# MCU.net
KiCad netlist of a schematic drawn in Altium Designer
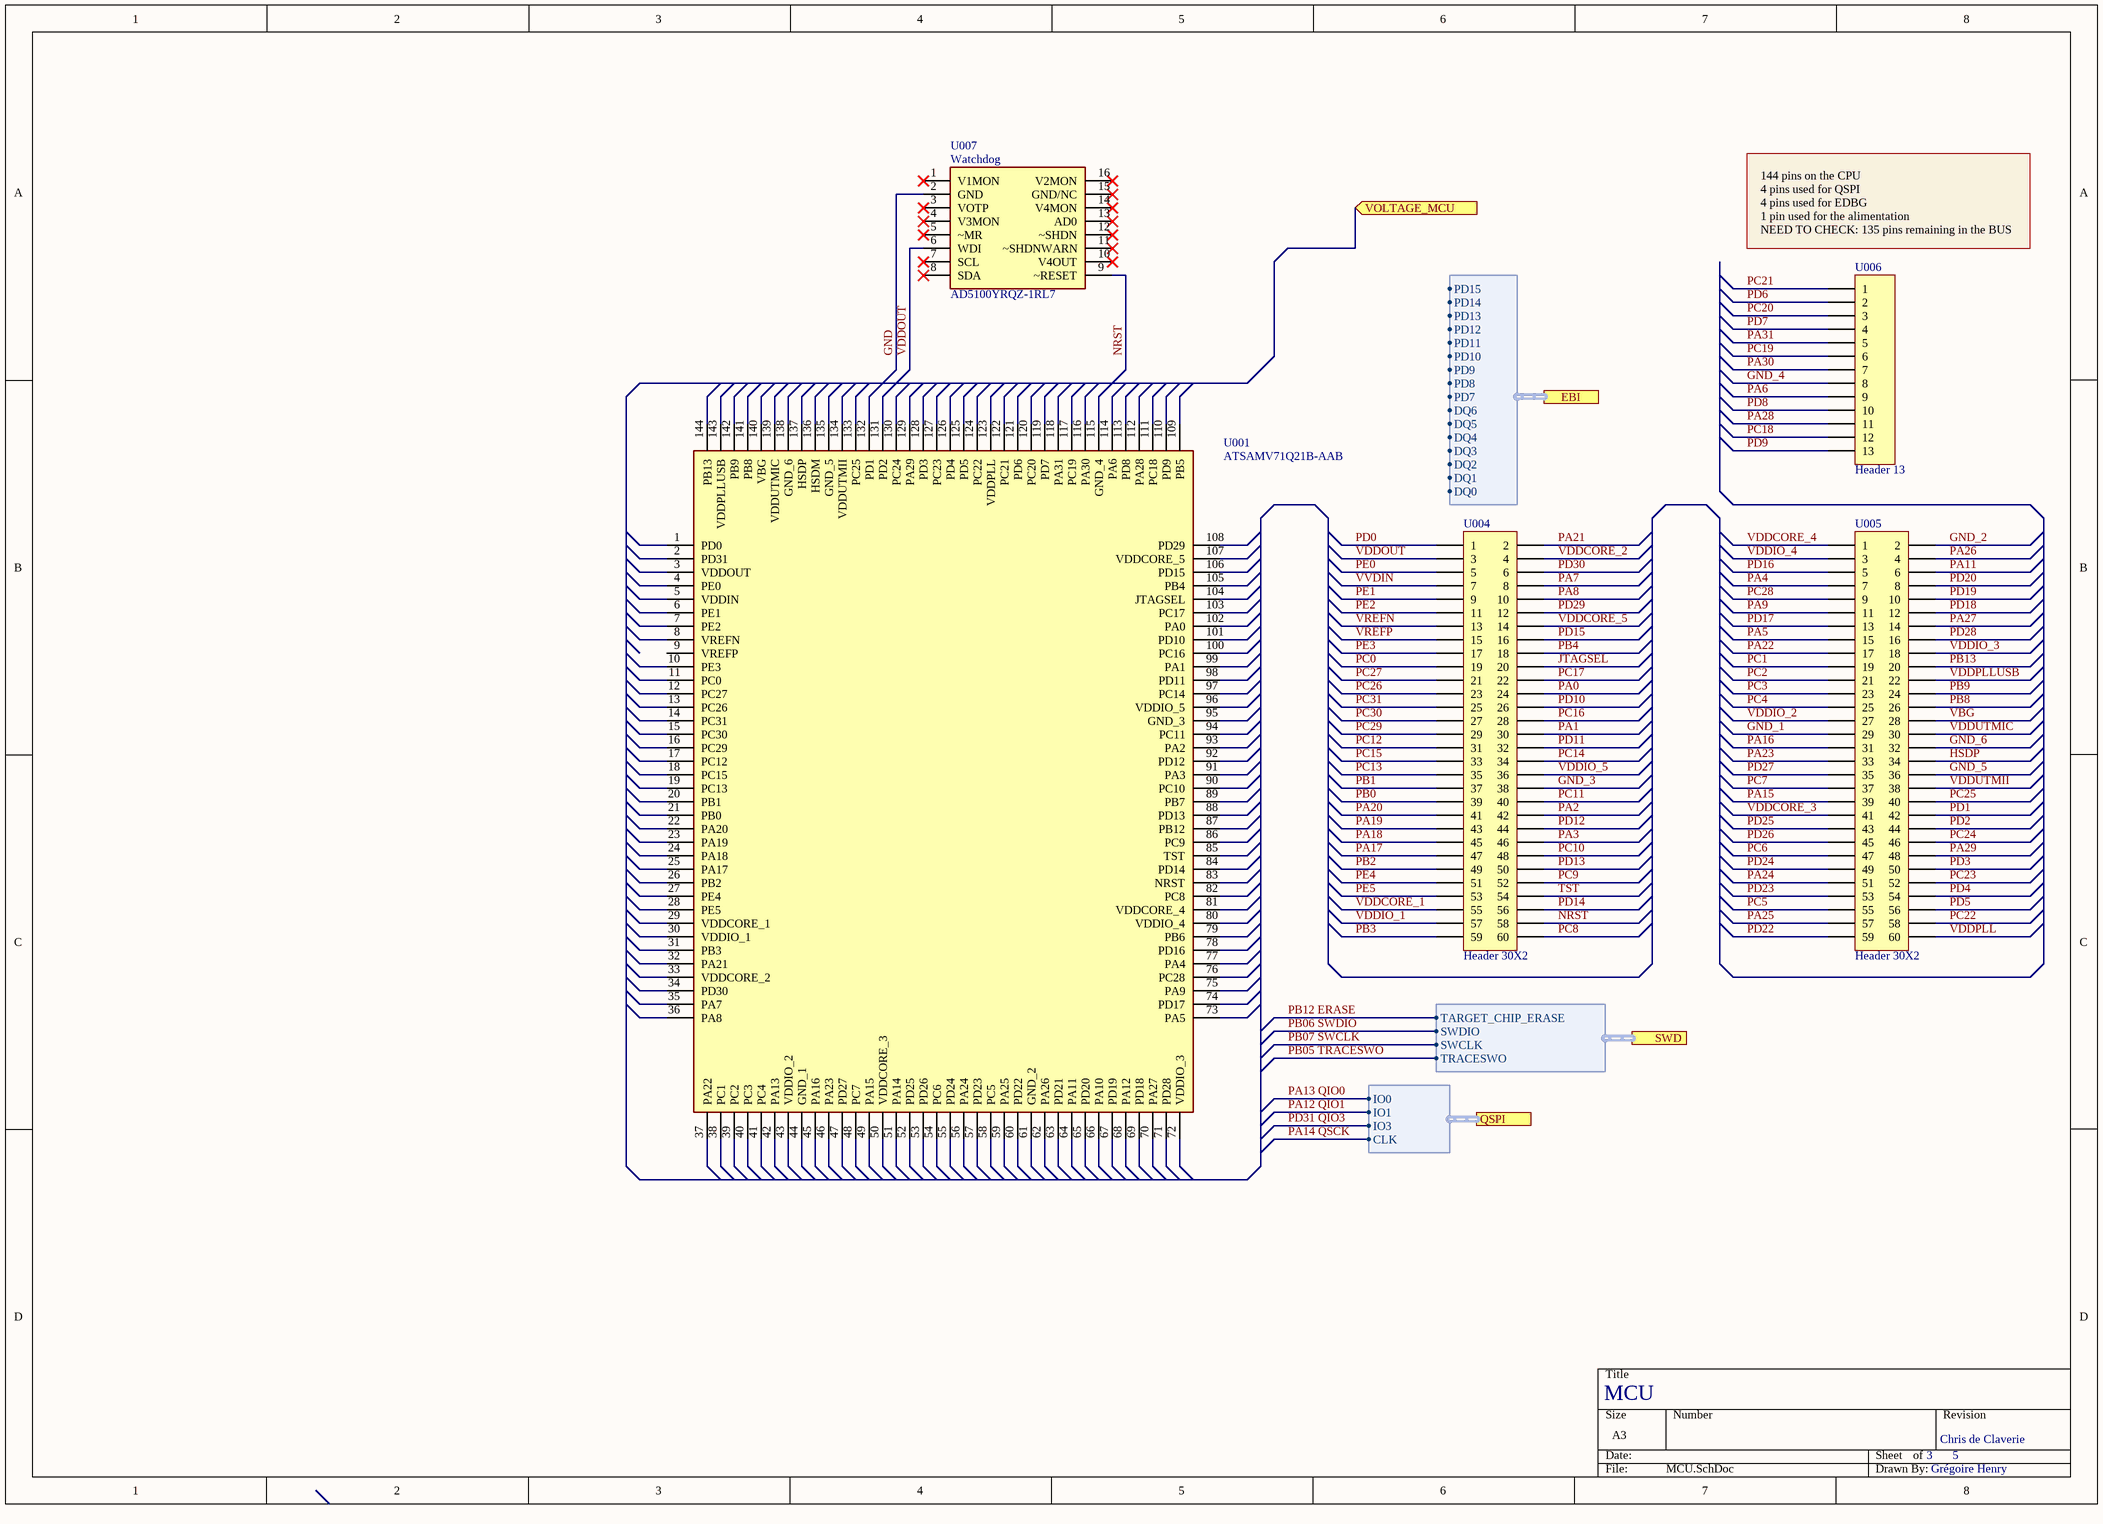
[diagram p0: MCU.SchDoc]

(export (version "E")
  (design (tool "Eeschema 10.0.6"))
  (components
    (comp (ref "U001")
      (value "ATSAMV71Q21B-AAB")
      (footprint "SamacSys:QFP50P2200X2200X160-144N")
      (description "Integrated Circuit")
      (fields (field (name "MOUSER PART NUMBER") "579-ATSAMV71Q21B-AAB"))
      (libsource (lib "*") (part "ATSAMV71Q21B-AAB"))
    )
    (comp (ref "U004")
      (value "Header 30X2")
      (footprint "HDR2X30")
      (description "Header, 30-Pin, Dual row")
      (fields (field (name "PUBLISHER") "Altium Limited"))
      (libsource (lib "Miscellaneous Connectors") (part "Header 30X2"))
    )
    (comp (ref "U005")
      (value "Header 30X2")
      (footprint "HDR2X30")
      (description "Header, 30-Pin, Dual row")
      (fields (field (name "PUBLISHER") "Altium Limited"))
      (libsource (lib "Miscellaneous Connectors") (part "Header 30X2"))
    )
    (comp (ref "U006")
      (value "Header 13")
      (footprint "HDR1X13")
      (description "Header, 13-Pin")
      (fields (field (name "PUBLISHER") "Altium Limited"))
      (libsource (lib "Miscellaneous Connectors") (part "Header 13"))
    )
    (comp (ref "U007")
      (value "AD5100YRQZ-1RL7")
      (footprint "SamacSys:SOP65P600X175-16N")
      (description "Integrated Circuit")
      (fields (field (name "MOUSER PART NUMBER") "584-AD5100YRQZ-1R7"))
      (libsource (lib "*") (part "AD5100YRQZ-1RL7"))
    )
  )
  (nets
    (net (code "2") (name "/GND") (class "Default")
      (node (ref "U007") (pin "2") (pinfunction "GND_2") (pintype "passive"))
    )
    (net (code "3") (name "/GND_1") (class "Default")
      (node (ref "U005") (pin "29") (pinfunction "29_29") (pintype "passive"))
    )
    (net (code "4") (name "/GND_2") (class "Default")
      (node (ref "U005") (pin "2") (pinfunction "2_2") (pintype "passive"))
    )
    (net (code "5") (name "/GND_3") (class "Default")
      (node (ref "U004") (pin "38") (pinfunction "38_38") (pintype "passive"))
    )
    (net (code "6") (name "/GND_4") (class "Default")
      (node (ref "U006") (pin "8") (pinfunction "8_8") (pintype "passive"))
    )
    (net (code "7") (name "/GND_5") (class "Default")
      (node (ref "U005") (pin "36") (pinfunction "36_36") (pintype "passive"))
    )
    (net (code "8") (name "/GND_6") (class "Default")
      (node (ref "U005") (pin "32") (pinfunction "32_32") (pintype "passive"))
    )
    (net (code "9") (name "/HSDP") (class "Default")
      (node (ref "U005") (pin "34") (pinfunction "34_34") (pintype "passive"))
    )
    (net (code "10") (name "/JTAGSEL") (class "Default")
      (node (ref "U004") (pin "20") (pinfunction "20_20") (pintype "passive"))
    )
    (net (code "11") (name "/NRST") (class "Default")
      (node (ref "U004") (pin "58") (pinfunction "58_58") (pintype "passive"))
      (node (ref "U007") (pin "9") (pinfunction "~RESET_9") (pintype "passive"))
    )
    (net (code "12") (name "/PA0") (class "Default")
      (node (ref "U004") (pin "24") (pinfunction "24_24") (pintype "passive"))
    )
    (net (code "13") (name "/PA1") (class "Default")
      (node (ref "U004") (pin "30") (pinfunction "30_30") (pintype "passive"))
    )
    (net (code "14") (name "/PA2") (class "Default")
      (node (ref "U004") (pin "42") (pinfunction "42_42") (pintype "passive"))
    )
    (net (code "15") (name "/PA3") (class "Default")
      (node (ref "U004") (pin "46") (pinfunction "46_46") (pintype "passive"))
    )
    (net (code "16") (name "/PA4") (class "Default")
      (node (ref "U005") (pin "7") (pinfunction "7_7") (pintype "passive"))
    )
    (net (code "17") (name "/PA5") (class "Default")
      (node (ref "U005") (pin "15") (pinfunction "15_15") (pintype "passive"))
    )
    (net (code "18") (name "/PA6") (class "Default")
      (node (ref "U006") (pin "9") (pinfunction "9_9") (pintype "passive"))
    )
    (net (code "19") (name "/PA7") (class "Default")
      (node (ref "U004") (pin "8") (pinfunction "8_8") (pintype "passive"))
    )
    (net (code "20") (name "/PA8") (class "Default")
      (node (ref "U004") (pin "10") (pinfunction "10_10") (pintype "passive"))
    )
    (net (code "21") (name "/PA9") (class "Default")
      (node (ref "U005") (pin "11") (pinfunction "11_11") (pintype "passive"))
    )
    (net (code "22") (name "/PA11") (class "Default")
      (node (ref "U005") (pin "6") (pinfunction "6_6") (pintype "passive"))
    )
    (net (code "26") (name "/PA15") (class "Default")
      (node (ref "U005") (pin "39") (pinfunction "39_39") (pintype "passive"))
    )
    (net (code "27") (name "/PA16") (class "Default")
      (node (ref "U005") (pin "31") (pinfunction "31_31") (pintype "passive"))
    )
    (net (code "28") (name "/PA17") (class "Default")
      (node (ref "U004") (pin "47") (pinfunction "47_47") (pintype "passive"))
    )
    (net (code "29") (name "/PA18") (class "Default")
      (node (ref "U004") (pin "45") (pinfunction "45_45") (pintype "passive"))
    )
    (net (code "30") (name "/PA19") (class "Default")
      (node (ref "U004") (pin "43") (pinfunction "43_43") (pintype "passive"))
    )
    (net (code "31") (name "/PA20") (class "Default")
      (node (ref "U004") (pin "41") (pinfunction "41_41") (pintype "passive"))
    )
    (net (code "32") (name "/PA21") (class "Default")
      (node (ref "U004") (pin "2") (pinfunction "2_2") (pintype "passive"))
    )
    (net (code "33") (name "/PA22") (class "Default")
      (node (ref "U005") (pin "17") (pinfunction "17_17") (pintype "passive"))
    )
    (net (code "34") (name "/PA23") (class "Default")
      (node (ref "U005") (pin "33") (pinfunction "33_33") (pintype "passive"))
    )
    (net (code "35") (name "/PA24") (class "Default")
      (node (ref "U005") (pin "51") (pinfunction "51_51") (pintype "passive"))
    )
    (net (code "36") (name "/PA25") (class "Default")
      (node (ref "U005") (pin "57") (pinfunction "57_57") (pintype "passive"))
    )
    (net (code "37") (name "/PA26") (class "Default")
      (node (ref "U005") (pin "4") (pinfunction "4_4") (pintype "passive"))
    )
    (net (code "38") (name "/PA27") (class "Default")
      (node (ref "U005") (pin "14") (pinfunction "14_14") (pintype "passive"))
    )
    (net (code "39") (name "/PA28") (class "Default")
      (node (ref "U006") (pin "11") (pinfunction "11_11") (pintype "passive"))
    )
    (net (code "40") (name "/PA29") (class "Default")
      (node (ref "U005") (pin "48") (pinfunction "48_48") (pintype "passive"))
    )
    (net (code "41") (name "/PA30") (class "Default")
      (node (ref "U006") (pin "7") (pinfunction "7_7") (pintype "passive"))
    )
    (net (code "42") (name "/PA31") (class "Default")
      (node (ref "U006") (pin "5") (pinfunction "5_5") (pintype "passive"))
    )
    (net (code "43") (name "/PB0") (class "Default")
      (node (ref "U004") (pin "39") (pinfunction "39_39") (pintype "passive"))
    )
    (net (code "44") (name "/PB1") (class "Default")
      (node (ref "U004") (pin "37") (pinfunction "37_37") (pintype "passive"))
    )
    (net (code "45") (name "/PB2") (class "Default")
      (node (ref "U004") (pin "49") (pinfunction "49_49") (pintype "passive"))
    )
    (net (code "46") (name "/PB3") (class "Default")
      (node (ref "U004") (pin "59") (pinfunction "59_59") (pintype "passive"))
    )
    (net (code "47") (name "/PB4") (class "Default")
      (node (ref "U004") (pin "18") (pinfunction "18_18") (pintype "passive"))
    )
    (net (code "51") (name "/PB8") (class "Default")
      (node (ref "U005") (pin "26") (pinfunction "26_26") (pintype "passive"))
    )
    (net (code "52") (name "/PB9") (class "Default")
      (node (ref "U005") (pin "24") (pinfunction "24_24") (pintype "passive"))
    )
    (net (code "54") (name "/PB13") (class "Default")
      (node (ref "U005") (pin "20") (pinfunction "20_20") (pintype "passive"))
    )
    (net (code "55") (name "/PC0") (class "Default")
      (node (ref "U004") (pin "19") (pinfunction "19_19") (pintype "passive"))
    )
    (net (code "56") (name "/PC1") (class "Default")
      (node (ref "U005") (pin "19") (pinfunction "19_19") (pintype "passive"))
    )
    (net (code "57") (name "/PC2") (class "Default")
      (node (ref "U005") (pin "21") (pinfunction "21_21") (pintype "passive"))
    )
    (net (code "58") (name "/PC3") (class "Default")
      (node (ref "U005") (pin "23") (pinfunction "23_23") (pintype "passive"))
    )
    (net (code "59") (name "/PC4") (class "Default")
      (node (ref "U005") (pin "25") (pinfunction "25_25") (pintype "passive"))
    )
    (net (code "60") (name "/PC5") (class "Default")
      (node (ref "U005") (pin "55") (pinfunction "55_55") (pintype "passive"))
    )
    (net (code "61") (name "/PC6") (class "Default")
      (node (ref "U005") (pin "47") (pinfunction "47_47") (pintype "passive"))
    )
    (net (code "62") (name "/PC7") (class "Default")
      (node (ref "U005") (pin "37") (pinfunction "37_37") (pintype "passive"))
    )
    (net (code "63") (name "/PC8") (class "Default")
      (node (ref "U004") (pin "60") (pinfunction "60_60") (pintype "passive"))
    )
    (net (code "64") (name "/PC9") (class "Default")
      (node (ref "U004") (pin "52") (pinfunction "52_52") (pintype "passive"))
    )
    (net (code "65") (name "/PC10") (class "Default")
      (node (ref "U004") (pin "48") (pinfunction "48_48") (pintype "passive"))
    )
    (net (code "66") (name "/PC11") (class "Default")
      (node (ref "U004") (pin "40") (pinfunction "40_40") (pintype "passive"))
    )
    (net (code "67") (name "/PC12") (class "Default")
      (node (ref "U004") (pin "31") (pinfunction "31_31") (pintype "passive"))
    )
    (net (code "68") (name "/PC13") (class "Default")
      (node (ref "U004") (pin "35") (pinfunction "35_35") (pintype "passive"))
    )
    (net (code "69") (name "/PC14") (class "Default")
      (node (ref "U004") (pin "34") (pinfunction "34_34") (pintype "passive"))
    )
    (net (code "70") (name "/PC15") (class "Default")
      (node (ref "U004") (pin "33") (pinfunction "33_33") (pintype "passive"))
    )
    (net (code "71") (name "/PC16") (class "Default")
      (node (ref "U004") (pin "28") (pinfunction "28_28") (pintype "passive"))
    )
    (net (code "72") (name "/PC17") (class "Default")
      (node (ref "U004") (pin "22") (pinfunction "22_22") (pintype "passive"))
    )
    (net (code "73") (name "/PC18") (class "Default")
      (node (ref "U006") (pin "12") (pinfunction "12_12") (pintype "passive"))
    )
    (net (code "74") (name "/PC19") (class "Default")
      (node (ref "U006") (pin "6") (pinfunction "6_6") (pintype "passive"))
    )
    (net (code "75") (name "/PC20") (class "Default")
      (node (ref "U006") (pin "3") (pinfunction "3_3") (pintype "passive"))
    )
    (net (code "76") (name "/PC21") (class "Default")
      (node (ref "U006") (pin "1") (pinfunction "1_1") (pintype "passive"))
    )
    (net (code "77") (name "/PC22") (class "Default")
      (node (ref "U005") (pin "58") (pinfunction "58_58") (pintype "passive"))
    )
    (net (code "78") (name "/PC23") (class "Default")
      (node (ref "U005") (pin "52") (pinfunction "52_52") (pintype "passive"))
    )
    (net (code "79") (name "/PC24") (class "Default")
      (node (ref "U005") (pin "46") (pinfunction "46_46") (pintype "passive"))
    )
    (net (code "80") (name "/PC25") (class "Default")
      (node (ref "U005") (pin "40") (pinfunction "40_40") (pintype "passive"))
    )
    (net (code "81") (name "/PC26") (class "Default")
      (node (ref "U004") (pin "23") (pinfunction "23_23") (pintype "passive"))
    )
    (net (code "82") (name "/PC27") (class "Default")
      (node (ref "U004") (pin "21") (pinfunction "21_21") (pintype "passive"))
    )
    (net (code "83") (name "/PC28") (class "Default")
      (node (ref "U005") (pin "9") (pinfunction "9_9") (pintype "passive"))
    )
    (net (code "84") (name "/PC29") (class "Default")
      (node (ref "U004") (pin "29") (pinfunction "29_29") (pintype "passive"))
    )
    (net (code "85") (name "/PC30") (class "Default")
      (node (ref "U004") (pin "27") (pinfunction "27_27") (pintype "passive"))
    )
    (net (code "86") (name "/PC31") (class "Default")
      (node (ref "U004") (pin "25") (pinfunction "25_25") (pintype "passive"))
    )
    (net (code "87") (name "/PD0") (class "Default")
      (node (ref "U004") (pin "1") (pinfunction "1_1") (pintype "passive"))
    )
    (net (code "88") (name "/PD1") (class "Default")
      (node (ref "U005") (pin "42") (pinfunction "42_42") (pintype "passive"))
    )
    (net (code "89") (name "/PD2") (class "Default")
      (node (ref "U005") (pin "44") (pinfunction "44_44") (pintype "passive"))
    )
    (net (code "90") (name "/PD3") (class "Default")
      (node (ref "U005") (pin "50") (pinfunction "50_50") (pintype "passive"))
    )
    (net (code "91") (name "/PD4") (class "Default")
      (node (ref "U005") (pin "54") (pinfunction "54_54") (pintype "passive"))
    )
    (net (code "92") (name "/PD5") (class "Default")
      (node (ref "U005") (pin "56") (pinfunction "56_56") (pintype "passive"))
    )
    (net (code "93") (name "/PD6") (class "Default")
      (node (ref "U006") (pin "2") (pinfunction "2_2") (pintype "passive"))
    )
    (net (code "94") (name "/PD7") (class "Default")
      (node (ref "U006") (pin "4") (pinfunction "4_4") (pintype "passive"))
    )
    (net (code "95") (name "/PD8") (class "Default")
      (node (ref "U006") (pin "10") (pinfunction "10_10") (pintype "passive"))
    )
    (net (code "96") (name "/PD9") (class "Default")
      (node (ref "U006") (pin "13") (pinfunction "13_13") (pintype "passive"))
    )
    (net (code "97") (name "/PD10") (class "Default")
      (node (ref "U004") (pin "26") (pinfunction "26_26") (pintype "passive"))
    )
    (net (code "98") (name "/PD11") (class "Default")
      (node (ref "U004") (pin "32") (pinfunction "32_32") (pintype "passive"))
    )
    (net (code "99") (name "/PD12") (class "Default")
      (node (ref "U004") (pin "44") (pinfunction "44_44") (pintype "passive"))
    )
    (net (code "100") (name "/PD13") (class "Default")
      (node (ref "U004") (pin "50") (pinfunction "50_50") (pintype "passive"))
    )
    (net (code "101") (name "/PD14") (class "Default")
      (node (ref "U004") (pin "56") (pinfunction "56_56") (pintype "passive"))
    )
    (net (code "102") (name "/PD15") (class "Default")
      (node (ref "U004") (pin "16") (pinfunction "16_16") (pintype "passive"))
    )
    (net (code "103") (name "/PD16") (class "Default")
      (node (ref "U005") (pin "5") (pinfunction "5_5") (pintype "passive"))
    )
    (net (code "104") (name "/PD17") (class "Default")
      (node (ref "U005") (pin "13") (pinfunction "13_13") (pintype "passive"))
    )
    (net (code "105") (name "/PD18") (class "Default")
      (node (ref "U005") (pin "12") (pinfunction "12_12") (pintype "passive"))
    )
    (net (code "106") (name "/PD19") (class "Default")
      (node (ref "U005") (pin "10") (pinfunction "10_10") (pintype "passive"))
    )
    (net (code "107") (name "/PD20") (class "Default")
      (node (ref "U005") (pin "8") (pinfunction "8_8") (pintype "passive"))
    )
    (net (code "108") (name "/PD22") (class "Default")
      (node (ref "U005") (pin "59") (pinfunction "59_59") (pintype "passive"))
    )
    (net (code "109") (name "/PD23") (class "Default")
      (node (ref "U005") (pin "53") (pinfunction "53_53") (pintype "passive"))
    )
    (net (code "110") (name "/PD24") (class "Default")
      (node (ref "U005") (pin "49") (pinfunction "49_49") (pintype "passive"))
    )
    (net (code "111") (name "/PD25") (class "Default")
      (node (ref "U005") (pin "43") (pinfunction "43_43") (pintype "passive"))
    )
    (net (code "112") (name "/PD26") (class "Default")
      (node (ref "U005") (pin "45") (pinfunction "45_45") (pintype "passive"))
    )
    (net (code "113") (name "/PD27") (class "Default")
      (node (ref "U005") (pin "35") (pinfunction "35_35") (pintype "passive"))
    )
    (net (code "114") (name "/PD28") (class "Default")
      (node (ref "U005") (pin "16") (pinfunction "16_16") (pintype "passive"))
    )
    (net (code "115") (name "/PD29") (class "Default")
      (node (ref "U004") (pin "12") (pinfunction "12_12") (pintype "passive"))
    )
    (net (code "116") (name "/PD30") (class "Default")
      (node (ref "U004") (pin "6") (pinfunction "6_6") (pintype "passive"))
    )
    (net (code "118") (name "/PE0") (class "Default")
      (node (ref "U004") (pin "5") (pinfunction "5_5") (pintype "passive"))
    )
    (net (code "119") (name "/PE1") (class "Default")
      (node (ref "U004") (pin "9") (pinfunction "9_9") (pintype "passive"))
    )
    (net (code "120") (name "/PE2") (class "Default")
      (node (ref "U004") (pin "11") (pinfunction "11_11") (pintype "passive"))
    )
    (net (code "121") (name "/PE3") (class "Default")
      (node (ref "U004") (pin "17") (pinfunction "17_17") (pintype "passive"))
    )
    (net (code "122") (name "/PE4") (class "Default")
      (node (ref "U004") (pin "51") (pinfunction "51_51") (pintype "passive"))
    )
    (net (code "123") (name "/PE5") (class "Default")
      (node (ref "U004") (pin "53") (pinfunction "53_53") (pintype "passive"))
    )
    (net (code "124") (name "/TST") (class "Default")
      (node (ref "U004") (pin "54") (pinfunction "54_54") (pintype "passive"))
    )
    (net (code "125") (name "/VBG") (class "Default")
      (node (ref "U005") (pin "28") (pinfunction "28_28") (pintype "passive"))
    )
    (net (code "126") (name "/VDDCORE_1") (class "Default")
      (node (ref "U004") (pin "55") (pinfunction "55_55") (pintype "passive"))
    )
    (net (code "127") (name "/VDDCORE_2") (class "Default")
      (node (ref "U004") (pin "4") (pinfunction "4_4") (pintype "passive"))
    )
    (net (code "128") (name "/VDDCORE_3") (class "Default")
      (node (ref "U005") (pin "41") (pinfunction "41_41") (pintype "passive"))
    )
    (net (code "129") (name "/VDDCORE_4") (class "Default")
      (node (ref "U005") (pin "1") (pinfunction "1_1") (pintype "passive"))
    )
    (net (code "130") (name "/VDDCORE_5") (class "Default")
      (node (ref "U004") (pin "14") (pinfunction "14_14") (pintype "passive"))
    )
    (net (code "131") (name "/VDDIO_1") (class "Default")
      (node (ref "U004") (pin "57") (pinfunction "57_57") (pintype "passive"))
    )
    (net (code "132") (name "/VDDIO_2") (class "Default")
      (node (ref "U005") (pin "27") (pinfunction "27_27") (pintype "passive"))
    )
    (net (code "133") (name "/VDDIO_3") (class "Default")
      (node (ref "U005") (pin "18") (pinfunction "18_18") (pintype "passive"))
    )
    (net (code "134") (name "/VDDIO_4") (class "Default")
      (node (ref "U005") (pin "3") (pinfunction "3_3") (pintype "passive"))
    )
    (net (code "135") (name "/VDDIO_5") (class "Default")
      (node (ref "U004") (pin "36") (pinfunction "36_36") (pintype "passive"))
    )
    (net (code "136") (name "/VDDOUT") (class "Default")
      (node (ref "U004") (pin "3") (pinfunction "3_3") (pintype "passive"))
      (node (ref "U007") (pin "6") (pinfunction "WDI_6") (pintype "passive"))
    )
    (net (code "137") (name "/VDDPLL") (class "Default")
      (node (ref "U005") (pin "60") (pinfunction "60_60") (pintype "passive"))
    )
    (net (code "138") (name "/VDDPLLUSB") (class "Default")
      (node (ref "U005") (pin "22") (pinfunction "22_22") (pintype "passive"))
    )
    (net (code "139") (name "/VDDUTMIC") (class "Default")
      (node (ref "U005") (pin "30") (pinfunction "30_30") (pintype "passive"))
    )
    (net (code "140") (name "/VDDUTMII") (class "Default")
      (node (ref "U005") (pin "38") (pinfunction "38_38") (pintype "passive"))
    )
    (net (code "142") (name "/VREFN") (class "Default")
      (node (ref "U004") (pin "13") (pinfunction "13_13") (pintype "passive"))
    )
    (net (code "143") (name "/VREFP") (class "Default")
      (node (ref "U004") (pin "15") (pinfunction "15_15") (pintype "passive"))
    )
    (net (code "144") (name "/VVDIN") (class "Default")
      (node (ref "U004") (pin "7") (pinfunction "7_7") (pintype "passive"))
    )
    (net (code "146") (name "unconnected-(U001-GND_1-Pad44)") (class "Default")
      (node (ref "U001") (pin "44") (pinfunction "GND_1_44") (pintype "passive"))
    )
    (net (code "147") (name "unconnected-(U001-GND_2-Pad61)") (class "Default")
      (node (ref "U001") (pin "61") (pinfunction "GND_2_61") (pintype "passive"))
    )
    (net (code "148") (name "unconnected-(U001-GND_3-Pad95)") (class "Default")
      (node (ref "U001") (pin "95") (pinfunction "GND_3_95") (pintype "passive"))
    )
    (net (code "149") (name "unconnected-(U001-GND_4-Pad115)") (class "Default")
      (node (ref "U001") (pin "115") (pinfunction "GND_4_115") (pintype "passive"))
    )
    (net (code "150") (name "unconnected-(U001-GND_5-Pad135)") (class "Default")
      (node (ref "U001") (pin "135") (pinfunction "GND_5_135") (pintype "passive"))
    )
    (net (code "151") (name "unconnected-(U001-GND_6-Pad138)") (class "Default")
      (node (ref "U001") (pin "138") (pinfunction "GND_6_138") (pintype "passive"))
    )
    (net (code "152") (name "unconnected-(U001-HSDM-Pad136)") (class "Default")
      (node (ref "U001") (pin "136") (pinfunction "HSDM_136") (pintype "passive"))
    )
    (net (code "153") (name "unconnected-(U001-HSDP-Pad137)") (class "Default")
      (node (ref "U001") (pin "137") (pinfunction "HSDP_137") (pintype "passive"))
    )
    (net (code "154") (name "unconnected-(U001-JTAGSEL-Pad104)") (class "Default")
      (node (ref "U001") (pin "104") (pinfunction "JTAGSEL_104") (pintype "passive"))
    )
    (net (code "155") (name "unconnected-(U001-NRST-Pad83)") (class "Default")
      (node (ref "U001") (pin "83") (pinfunction "NRST_83") (pintype "passive"))
    )
    (net (code "156") (name "unconnected-(U001-PA0-Pad102)") (class "Default")
      (node (ref "U001") (pin "102") (pinfunction "PA0_102") (pintype "passive"))
    )
    (net (code "157") (name "unconnected-(U001-PA1-Pad99)") (class "Default")
      (node (ref "U001") (pin "99") (pinfunction "PA1_99") (pintype "passive"))
    )
    (net (code "158") (name "unconnected-(U001-PA2-Pad93)") (class "Default")
      (node (ref "U001") (pin "93") (pinfunction "PA2_93") (pintype "passive"))
    )
    (net (code "159") (name "unconnected-(U001-PA3-Pad91)") (class "Default")
      (node (ref "U001") (pin "91") (pinfunction "PA3_91") (pintype "passive"))
    )
    (net (code "160") (name "unconnected-(U001-PA4-Pad77)") (class "Default")
      (node (ref "U001") (pin "77") (pinfunction "PA4_77") (pintype "passive"))
    )
    (net (code "161") (name "unconnected-(U001-PA5-Pad73)") (class "Default")
      (node (ref "U001") (pin "73") (pinfunction "PA5_73") (pintype "passive"))
    )
    (net (code "162") (name "unconnected-(U001-PA6-Pad114)") (class "Default")
      (node (ref "U001") (pin "114") (pinfunction "PA6_114") (pintype "passive"))
    )
    (net (code "163") (name "unconnected-(U001-PA7-Pad35)") (class "Default")
      (node (ref "U001") (pin "35") (pinfunction "PA7_35") (pintype "passive"))
    )
    (net (code "164") (name "unconnected-(U001-PA8-Pad36)") (class "Default")
      (node (ref "U001") (pin "36") (pinfunction "PA8_36") (pintype "passive"))
    )
    (net (code "165") (name "unconnected-(U001-PA9-Pad75)") (class "Default")
      (node (ref "U001") (pin "75") (pinfunction "PA9_75") (pintype "passive"))
    )
    (net (code "166") (name "unconnected-(U001-PA10-Pad66)") (class "Default")
      (node (ref "U001") (pin "66") (pinfunction "PA10_66") (pintype "passive"))
    )
    (net (code "167") (name "unconnected-(U001-PA11-Pad64)") (class "Default")
      (node (ref "U001") (pin "64") (pinfunction "PA11_64") (pintype "passive"))
    )
    (net (code "168") (name "unconnected-(U001-PA12-Pad68)") (class "Default")
      (node (ref "U001") (pin "68") (pinfunction "PA12_68") (pintype "passive"))
    )
    (net (code "169") (name "unconnected-(U001-PA13-Pad42)") (class "Default")
      (node (ref "U001") (pin "42") (pinfunction "PA13_42") (pintype "passive"))
    )
    (net (code "170") (name "unconnected-(U001-PA14-Pad51)") (class "Default")
      (node (ref "U001") (pin "51") (pinfunction "PA14_51") (pintype "passive"))
    )
    (net (code "171") (name "unconnected-(U001-PA15-Pad49)") (class "Default")
      (node (ref "U001") (pin "49") (pinfunction "PA15_49") (pintype "passive"))
    )
    (net (code "172") (name "unconnected-(U001-PA16-Pad45)") (class "Default")
      (node (ref "U001") (pin "45") (pinfunction "PA16_45") (pintype "passive"))
    )
    (net (code "173") (name "unconnected-(U001-PA17-Pad25)") (class "Default")
      (node (ref "U001") (pin "25") (pinfunction "PA17_25") (pintype "passive"))
    )
    (net (code "174") (name "unconnected-(U001-PA18-Pad24)") (class "Default")
      (node (ref "U001") (pin "24") (pinfunction "PA18_24") (pintype "passive"))
    )
    (net (code "175") (name "unconnected-(U001-PA19-Pad23)") (class "Default")
      (node (ref "U001") (pin "23") (pinfunction "PA19_23") (pintype "passive"))
    )
    (net (code "176") (name "unconnected-(U001-PA20-Pad22)") (class "Default")
      (node (ref "U001") (pin "22") (pinfunction "PA20_22") (pintype "passive"))
    )
    (net (code "177") (name "unconnected-(U001-PA21-Pad32)") (class "Default")
      (node (ref "U001") (pin "32") (pinfunction "PA21_32") (pintype "passive"))
    )
    (net (code "178") (name "unconnected-(U001-PA22-Pad37)") (class "Default")
      (node (ref "U001") (pin "37") (pinfunction "PA22_37") (pintype "passive"))
    )
    (net (code "179") (name "unconnected-(U001-PA23-Pad46)") (class "Default")
      (node (ref "U001") (pin "46") (pinfunction "PA23_46") (pintype "passive"))
    )
    (net (code "180") (name "unconnected-(U001-PA24-Pad56)") (class "Default")
      (node (ref "U001") (pin "56") (pinfunction "PA24_56") (pintype "passive"))
    )
    (net (code "181") (name "unconnected-(U001-PA25-Pad59)") (class "Default")
      (node (ref "U001") (pin "59") (pinfunction "PA25_59") (pintype "passive"))
    )
    (net (code "182") (name "unconnected-(U001-PA26-Pad62)") (class "Default")
      (node (ref "U001") (pin "62") (pinfunction "PA26_62") (pintype "passive"))
    )
    (net (code "183") (name "unconnected-(U001-PA27-Pad70)") (class "Default")
      (node (ref "U001") (pin "70") (pinfunction "PA27_70") (pintype "passive"))
    )
    (net (code "184") (name "unconnected-(U001-PA28-Pad112)") (class "Default")
      (node (ref "U001") (pin "112") (pinfunction "PA28_112") (pintype "passive"))
    )
    (net (code "185") (name "unconnected-(U001-PA29-Pad129)") (class "Default")
      (node (ref "U001") (pin "129") (pinfunction "PA29_129") (pintype "passive"))
    )
    (net (code "186") (name "unconnected-(U001-PA30-Pad116)") (class "Default")
      (node (ref "U001") (pin "116") (pinfunction "PA30_116") (pintype "passive"))
    )
    (net (code "187") (name "unconnected-(U001-PA31-Pad118)") (class "Default")
      (node (ref "U001") (pin "118") (pinfunction "PA31_118") (pintype "passive"))
    )
    (net (code "188") (name "unconnected-(U001-PB0-Pad21)") (class "Default")
      (node (ref "U001") (pin "21") (pinfunction "PB0_21") (pintype "passive"))
    )
    (net (code "189") (name "unconnected-(U001-PB1-Pad20)") (class "Default")
      (node (ref "U001") (pin "20") (pinfunction "PB1_20") (pintype "passive"))
    )
    (net (code "190") (name "unconnected-(U001-PB2-Pad26)") (class "Default")
      (node (ref "U001") (pin "26") (pinfunction "PB2_26") (pintype "passive"))
    )
    (net (code "191") (name "unconnected-(U001-PB3-Pad31)") (class "Default")
      (node (ref "U001") (pin "31") (pinfunction "PB3_31") (pintype "passive"))
    )
    (net (code "192") (name "unconnected-(U001-PB4-Pad105)") (class "Default")
      (node (ref "U001") (pin "105") (pinfunction "PB4_105") (pintype "passive"))
    )
    (net (code "193") (name "unconnected-(U001-PB5-Pad109)") (class "Default")
      (node (ref "U001") (pin "109") (pinfunction "PB5_109") (pintype "passive"))
    )
    (net (code "194") (name "unconnected-(U001-PB6-Pad79)") (class "Default")
      (node (ref "U001") (pin "79") (pinfunction "PB6_79") (pintype "passive"))
    )
    (net (code "195") (name "unconnected-(U001-PB7-Pad89)") (class "Default")
      (node (ref "U001") (pin "89") (pinfunction "PB7_89") (pintype "passive"))
    )
    (net (code "196") (name "unconnected-(U001-PB8-Pad141)") (class "Default")
      (node (ref "U001") (pin "141") (pinfunction "PB8_141") (pintype "passive"))
    )
    (net (code "197") (name "unconnected-(U001-PB9-Pad142)") (class "Default")
      (node (ref "U001") (pin "142") (pinfunction "PB9_142") (pintype "passive"))
    )
    (net (code "198") (name "unconnected-(U001-PB12-Pad87)") (class "Default")
      (node (ref "U001") (pin "87") (pinfunction "PB12_87") (pintype "passive"))
    )
    (net (code "199") (name "unconnected-(U001-PB13-Pad144)") (class "Default")
      (node (ref "U001") (pin "144") (pinfunction "PB13_144") (pintype "passive"))
    )
    (net (code "200") (name "unconnected-(U001-PC0-Pad11)") (class "Default")
      (node (ref "U001") (pin "11") (pinfunction "PC0_11") (pintype "passive"))
    )
    (net (code "201") (name "unconnected-(U001-PC1-Pad38)") (class "Default")
      (node (ref "U001") (pin "38") (pinfunction "PC1_38") (pintype "passive"))
    )
    (net (code "202") (name "unconnected-(U001-PC2-Pad39)") (class "Default")
      (node (ref "U001") (pin "39") (pinfunction "PC2_39") (pintype "passive"))
    )
    (net (code "203") (name "unconnected-(U001-PC3-Pad40)") (class "Default")
      (node (ref "U001") (pin "40") (pinfunction "PC3_40") (pintype "passive"))
    )
    (net (code "204") (name "unconnected-(U001-PC4-Pad41)") (class "Default")
      (node (ref "U001") (pin "41") (pinfunction "PC4_41") (pintype "passive"))
    )
    (net (code "205") (name "unconnected-(U001-PC5-Pad58)") (class "Default")
      (node (ref "U001") (pin "58") (pinfunction "PC5_58") (pintype "passive"))
    )
    (net (code "206") (name "unconnected-(U001-PC6-Pad54)") (class "Default")
      (node (ref "U001") (pin "54") (pinfunction "PC6_54") (pintype "passive"))
    )
    (net (code "207") (name "unconnected-(U001-PC7-Pad48)") (class "Default")
      (node (ref "U001") (pin "48") (pinfunction "PC7_48") (pintype "passive"))
    )
    (net (code "208") (name "unconnected-(U001-PC8-Pad82)") (class "Default")
      (node (ref "U001") (pin "82") (pinfunction "PC8_82") (pintype "passive"))
    )
    (net (code "209") (name "unconnected-(U001-PC9-Pad86)") (class "Default")
      (node (ref "U001") (pin "86") (pinfunction "PC9_86") (pintype "passive"))
    )
    (net (code "210") (name "unconnected-(U001-PC10-Pad90)") (class "Default")
      (node (ref "U001") (pin "90") (pinfunction "PC10_90") (pintype "passive"))
    )
    (net (code "211") (name "unconnected-(U001-PC11-Pad94)") (class "Default")
      (node (ref "U001") (pin "94") (pinfunction "PC11_94") (pintype "passive"))
    )
    (net (code "212") (name "unconnected-(U001-PC12-Pad17)") (class "Default")
      (node (ref "U001") (pin "17") (pinfunction "PC12_17") (pintype "passive"))
    )
    (net (code "213") (name "unconnected-(U001-PC13-Pad19)") (class "Default")
      (node (ref "U001") (pin "19") (pinfunction "PC13_19") (pintype "passive"))
    )
    (net (code "214") (name "unconnected-(U001-PC14-Pad97)") (class "Default")
      (node (ref "U001") (pin "97") (pinfunction "PC14_97") (pintype "passive"))
    )
    (net (code "215") (name "unconnected-(U001-PC15-Pad18)") (class "Default")
      (node (ref "U001") (pin "18") (pinfunction "PC15_18") (pintype "passive"))
    )
    (net (code "216") (name "unconnected-(U001-PC16-Pad100)") (class "Default")
      (node (ref "U001") (pin "100") (pinfunction "PC16_100") (pintype "passive"))
    )
    (net (code "217") (name "unconnected-(U001-PC17-Pad103)") (class "Default")
      (node (ref "U001") (pin "103") (pinfunction "PC17_103") (pintype "passive"))
    )
    (net (code "218") (name "unconnected-(U001-PC18-Pad111)") (class "Default")
      (node (ref "U001") (pin "111") (pinfunction "PC18_111") (pintype "passive"))
    )
    (net (code "219") (name "unconnected-(U001-PC19-Pad117)") (class "Default")
      (node (ref "U001") (pin "117") (pinfunction "PC19_117") (pintype "passive"))
    )
    (net (code "220") (name "unconnected-(U001-PC20-Pad120)") (class "Default")
      (node (ref "U001") (pin "120") (pinfunction "PC20_120") (pintype "passive"))
    )
    (net (code "221") (name "unconnected-(U001-PC21-Pad122)") (class "Default")
      (node (ref "U001") (pin "122") (pinfunction "PC21_122") (pintype "passive"))
    )
    (net (code "222") (name "unconnected-(U001-PC22-Pad124)") (class "Default")
      (node (ref "U001") (pin "124") (pinfunction "PC22_124") (pintype "passive"))
    )
    (net (code "223") (name "unconnected-(U001-PC23-Pad127)") (class "Default")
      (node (ref "U001") (pin "127") (pinfunction "PC23_127") (pintype "passive"))
    )
    (net (code "224") (name "unconnected-(U001-PC24-Pad130)") (class "Default")
      (node (ref "U001") (pin "130") (pinfunction "PC24_130") (pintype "passive"))
    )
    (net (code "225") (name "unconnected-(U001-PC25-Pad133)") (class "Default")
      (node (ref "U001") (pin "133") (pinfunction "PC25_133") (pintype "passive"))
    )
    (net (code "226") (name "unconnected-(U001-PC26-Pad13)") (class "Default")
      (node (ref "U001") (pin "13") (pinfunction "PC26_13") (pintype "passive"))
    )
    (net (code "227") (name "unconnected-(U001-PC27-Pad12)") (class "Default")
      (node (ref "U001") (pin "12") (pinfunction "PC27_12") (pintype "passive"))
    )
    (net (code "228") (name "unconnected-(U001-PC28-Pad76)") (class "Default")
      (node (ref "U001") (pin "76") (pinfunction "PC28_76") (pintype "passive"))
    )
    (net (code "229") (name "unconnected-(U001-PC29-Pad16)") (class "Default")
      (node (ref "U001") (pin "16") (pinfunction "PC29_16") (pintype "passive"))
    )
    (net (code "230") (name "unconnected-(U001-PC30-Pad15)") (class "Default")
      (node (ref "U001") (pin "15") (pinfunction "PC30_15") (pintype "passive"))
    )
    (net (code "231") (name "unconnected-(U001-PC31-Pad14)") (class "Default")
      (node (ref "U001") (pin "14") (pinfunction "PC31_14") (pintype "passive"))
    )
    (net (code "232") (name "unconnected-(U001-PD0-Pad1)") (class "Default")
      (node (ref "U001") (pin "1") (pinfunction "PD0_1") (pintype "passive"))
    )
    (net (code "233") (name "unconnected-(U001-PD1-Pad132)") (class "Default")
      (node (ref "U001") (pin "132") (pinfunction "PD1_132") (pintype "passive"))
    )
    (net (code "234") (name "unconnected-(U001-PD2-Pad131)") (class "Default")
      (node (ref "U001") (pin "131") (pinfunction "PD2_131") (pintype "passive"))
    )
    (net (code "235") (name "unconnected-(U001-PD3-Pad128)") (class "Default")
      (node (ref "U001") (pin "128") (pinfunction "PD3_128") (pintype "passive"))
    )
    (net (code "236") (name "unconnected-(U001-PD4-Pad126)") (class "Default")
      (node (ref "U001") (pin "126") (pinfunction "PD4_126") (pintype "passive"))
    )
    (net (code "237") (name "unconnected-(U001-PD5-Pad125)") (class "Default")
      (node (ref "U001") (pin "125") (pinfunction "PD5_125") (pintype "passive"))
    )
    (net (code "238") (name "unconnected-(U001-PD6-Pad121)") (class "Default")
      (node (ref "U001") (pin "121") (pinfunction "PD6_121") (pintype "passive"))
    )
    (net (code "239") (name "unconnected-(U001-PD7-Pad119)") (class "Default")
      (node (ref "U001") (pin "119") (pinfunction "PD7_119") (pintype "passive"))
    )
    (net (code "240") (name "unconnected-(U001-PD8-Pad113)") (class "Default")
      (node (ref "U001") (pin "113") (pinfunction "PD8_113") (pintype "passive"))
    )
    (net (code "241") (name "unconnected-(U001-PD9-Pad110)") (class "Default")
      (node (ref "U001") (pin "110") (pinfunction "PD9_110") (pintype "passive"))
    )
    (net (code "242") (name "unconnected-(U001-PD10-Pad101)") (class "Default")
      (node (ref "U001") (pin "101") (pinfunction "PD10_101") (pintype "passive"))
    )
    (net (code "243") (name "unconnected-(U001-PD11-Pad98)") (class "Default")
      (node (ref "U001") (pin "98") (pinfunction "PD11_98") (pintype "passive"))
    )
    (net (code "244") (name "unconnected-(U001-PD12-Pad92)") (class "Default")
      (node (ref "U001") (pin "92") (pinfunction "PD12_92") (pintype "passive"))
    )
    (net (code "245") (name "unconnected-(U001-PD13-Pad88)") (class "Default")
      (node (ref "U001") (pin "88") (pinfunction "PD13_88") (pintype "passive"))
    )
    (net (code "246") (name "unconnected-(U001-PD14-Pad84)") (class "Default")
      (node (ref "U001") (pin "84") (pinfunction "PD14_84") (pintype "passive"))
    )
    (net (code "247") (name "unconnected-(U001-PD15-Pad106)") (class "Default")
      (node (ref "U001") (pin "106") (pinfunction "PD15_106") (pintype "passive"))
    )
    (net (code "248") (name "unconnected-(U001-PD16-Pad78)") (class "Default")
      (node (ref "U001") (pin "78") (pinfunction "PD16_78") (pintype "passive"))
    )
    (net (code "249") (name "unconnected-(U001-PD17-Pad74)") (class "Default")
      (node (ref "U001") (pin "74") (pinfunction "PD17_74") (pintype "passive"))
    )
    (net (code "250") (name "unconnected-(U001-PD18-Pad69)") (class "Default")
      (node (ref "U001") (pin "69") (pinfunction "PD18_69") (pintype "passive"))
    )
    (net (code "251") (name "unconnected-(U001-PD19-Pad67)") (class "Default")
      (node (ref "U001") (pin "67") (pinfunction "PD19_67") (pintype "passive"))
    )
    (net (code "252") (name "unconnected-(U001-PD20-Pad65)") (class "Default")
      (node (ref "U001") (pin "65") (pinfunction "PD20_65") (pintype "passive"))
    )
    (net (code "253") (name "unconnected-(U001-PD21-Pad63)") (class "Default")
      (node (ref "U001") (pin "63") (pinfunction "PD21_63") (pintype "passive"))
    )
    (net (code "254") (name "unconnected-(U001-PD22-Pad60)") (class "Default")
      (node (ref "U001") (pin "60") (pinfunction "PD22_60") (pintype "passive"))
    )
    (net (code "255") (name "unconnected-(U001-PD23-Pad57)") (class "Default")
      (node (ref "U001") (pin "57") (pinfunction "PD23_57") (pintype "passive"))
    )
    (net (code "256") (name "unconnected-(U001-PD24-Pad55)") (class "Default")
      (node (ref "U001") (pin "55") (pinfunction "PD24_55") (pintype "passive"))
    )
    (net (code "257") (name "unconnected-(U001-PD25-Pad52)") (class "Default")
      (node (ref "U001") (pin "52") (pinfunction "PD25_52") (pintype "passive"))
    )
    (net (code "258") (name "unconnected-(U001-PD26-Pad53)") (class "Default")
      (node (ref "U001") (pin "53") (pinfunction "PD26_53") (pintype "passive"))
    )
    (net (code "259") (name "unconnected-(U001-PD27-Pad47)") (class "Default")
      (node (ref "U001") (pin "47") (pinfunction "PD27_47") (pintype "passive"))
    )
    (net (code "260") (name "unconnected-(U001-PD28-Pad71)") (class "Default")
      (node (ref "U001") (pin "71") (pinfunction "PD28_71") (pintype "passive"))
    )
    (net (code "261") (name "unconnected-(U001-PD29-Pad108)") (class "Default")
      (node (ref "U001") (pin "108") (pinfunction "PD29_108") (pintype "passive"))
    )
    (net (code "262") (name "unconnected-(U001-PD30-Pad34)") (class "Default")
      (node (ref "U001") (pin "34") (pinfunction "PD30_34") (pintype "passive"))
    )
    (net (code "263") (name "unconnected-(U001-PD31-Pad2)") (class "Default")
      (node (ref "U001") (pin "2") (pinfunction "PD31_2") (pintype "passive"))
    )
    (net (code "264") (name "unconnected-(U001-PE0-Pad4)") (class "Default")
      (node (ref "U001") (pin "4") (pinfunction "PE0_4") (pintype "passive"))
    )
    (net (code "265") (name "unconnected-(U001-PE1-Pad6)") (class "Default")
      (node (ref "U001") (pin "6") (pinfunction "PE1_6") (pintype "passive"))
    )
    (net (code "266") (name "unconnected-(U001-PE2-Pad7)") (class "Default")
      (node (ref "U001") (pin "7") (pinfunction "PE2_7") (pintype "passive"))
    )
    (net (code "267") (name "unconnected-(U001-PE3-Pad10)") (class "Default")
      (node (ref "U001") (pin "10") (pinfunction "PE3_10") (pintype "passive"))
    )
    (net (code "268") (name "unconnected-(U001-PE4-Pad27)") (class "Default")
      (node (ref "U001") (pin "27") (pinfunction "PE4_27") (pintype "passive"))
    )
    (net (code "269") (name "unconnected-(U001-PE5-Pad28)") (class "Default")
      (node (ref "U001") (pin "28") (pinfunction "PE5_28") (pintype "passive"))
    )
    (net (code "270") (name "unconnected-(U001-TST-Pad85)") (class "Default")
      (node (ref "U001") (pin "85") (pinfunction "TST_85") (pintype "passive"))
    )
    (net (code "271") (name "unconnected-(U001-VBG-Pad140)") (class "Default")
      (node (ref "U001") (pin "140") (pinfunction "VBG_140") (pintype "passive"))
    )
    (net (code "272") (name "unconnected-(U001-VDDCORE_1-Pad29)") (class "Default")
      (node (ref "U001") (pin "29") (pinfunction "VDDCORE_1_29") (pintype "passive"))
    )
    (net (code "273") (name "unconnected-(U001-VDDCORE_2-Pad33)") (class "Default")
      (node (ref "U001") (pin "33") (pinfunction "VDDCORE_2_33") (pintype "passive"))
    )
    (net (code "274") (name "unconnected-(U001-VDDCORE_3-Pad50)") (class "Default")
      (node (ref "U001") (pin "50") (pinfunction "VDDCORE_3_50") (pintype "passive"))
    )
    (net (code "275") (name "unconnected-(U001-VDDCORE_4-Pad81)") (class "Default")
      (node (ref "U001") (pin "81") (pinfunction "VDDCORE_4_81") (pintype "passive"))
    )
    (net (code "276") (name "unconnected-(U001-VDDCORE_5-Pad107)") (class "Default")
      (node (ref "U001") (pin "107") (pinfunction "VDDCORE_5_107") (pintype "passive"))
    )
    (net (code "277") (name "unconnected-(U001-VDDIN-Pad5)") (class "Default")
      (node (ref "U001") (pin "5") (pinfunction "VDDIN_5") (pintype "passive"))
    )
    (net (code "278") (name "unconnected-(U001-VDDIO_1-Pad30)") (class "Default")
      (node (ref "U001") (pin "30") (pinfunction "VDDIO_1_30") (pintype "passive"))
    )
    (net (code "279") (name "unconnected-(U001-VDDIO_2-Pad43)") (class "Default")
      (node (ref "U001") (pin "43") (pinfunction "VDDIO_2_43") (pintype "passive"))
    )
    (net (code "280") (name "unconnected-(U001-VDDIO_3-Pad72)") (class "Default")
      (node (ref "U001") (pin "72") (pinfunction "VDDIO_3_72") (pintype "passive"))
    )
    (net (code "281") (name "unconnected-(U001-VDDIO_4-Pad80)") (class "Default")
      (node (ref "U001") (pin "80") (pinfunction "VDDIO_4_80") (pintype "passive"))
    )
    (net (code "282") (name "unconnected-(U001-VDDIO_5-Pad96)") (class "Default")
      (node (ref "U001") (pin "96") (pinfunction "VDDIO_5_96") (pintype "passive"))
    )
    (net (code "283") (name "unconnected-(U001-VDDOUT-Pad3)") (class "Default")
      (node (ref "U001") (pin "3") (pinfunction "VDDOUT_3") (pintype "passive"))
    )
    (net (code "284") (name "unconnected-(U001-VDDPLL-Pad123)") (class "Default")
      (node (ref "U001") (pin "123") (pinfunction "VDDPLL_123") (pintype "passive"))
    )
    (net (code "285") (name "unconnected-(U001-VDDPLLUSB-Pad143)") (class "Default")
      (node (ref "U001") (pin "143") (pinfunction "VDDPLLUSB_143") (pintype "passive"))
    )
    (net (code "286") (name "unconnected-(U001-VDDUTMIC-Pad139)") (class "Default")
      (node (ref "U001") (pin "139") (pinfunction "VDDUTMIC_139") (pintype "passive"))
    )
    (net (code "287") (name "unconnected-(U001-VDDUTMII-Pad134)") (class "Default")
      (node (ref "U001") (pin "134") (pinfunction "VDDUTMII_134") (pintype "passive"))
    )
    (net (code "288") (name "unconnected-(U001-VREFN-Pad8)") (class "Default")
      (node (ref "U001") (pin "8") (pinfunction "VREFN_8") (pintype "passive"))
    )
    (net (code "289") (name "unconnected-(U001-VREFP-Pad9)") (class "Default")
      (node (ref "U001") (pin "9") (pinfunction "VREFP_9") (pintype "passive"))
    )
    (net (code "290") (name "unconnected-(U007-AD0-Pad13)") (class "Default")
      (node (ref "U007") (pin "13") (pinfunction "AD0_13") (pintype "passive+no_connect"))
    )
    (net (code "291") (name "unconnected-(U007-GND{slash}NC-Pad15)") (class "Default")
      (node (ref "U007") (pin "15") (pinfunction "GND/NC_15") (pintype "passive+no_connect"))
    )
    (net (code "292") (name "unconnected-(U007-SCL-Pad7)") (class "Default")
      (node (ref "U007") (pin "7") (pinfunction "SCL_7") (pintype "passive+no_connect"))
    )
    (net (code "293") (name "unconnected-(U007-SDA-Pad8)") (class "Default")
      (node (ref "U007") (pin "8") (pinfunction "SDA_8") (pintype "passive+no_connect"))
    )
    (net (code "294") (name "unconnected-(U007-V1MON-Pad1)") (class "Default")
      (node (ref "U007") (pin "1") (pinfunction "V1MON_1") (pintype "passive+no_connect"))
    )
    (net (code "295") (name "unconnected-(U007-V2MON-Pad16)") (class "Default")
      (node (ref "U007") (pin "16") (pinfunction "V2MON_16") (pintype "passive+no_connect"))
    )
    (net (code "296") (name "unconnected-(U007-V3MON-Pad4)") (class "Default")
      (node (ref "U007") (pin "4") (pinfunction "V3MON_4") (pintype "passive+no_connect"))
    )
    (net (code "297") (name "unconnected-(U007-V4MON-Pad14)") (class "Default")
      (node (ref "U007") (pin "14") (pinfunction "V4MON_14") (pintype "passive+no_connect"))
    )
    (net (code "298") (name "unconnected-(U007-V4OUT-Pad10)") (class "Default")
      (node (ref "U007") (pin "10") (pinfunction "V4OUT_10") (pintype "passive+no_connect"))
    )
    (net (code "299") (name "unconnected-(U007-VOTP-Pad3)") (class "Default")
      (node (ref "U007") (pin "3") (pinfunction "VOTP_3") (pintype "passive+no_connect"))
    )
    (net (code "300") (name "unconnected-(U007-~MR-Pad5)") (class "Default")
      (node (ref "U007") (pin "5") (pinfunction "~MR_5") (pintype "passive+no_connect"))
    )
    (net (code "301") (name "unconnected-(U007-~SHDN-Pad12)") (class "Default")
      (node (ref "U007") (pin "12") (pinfunction "~SHDN_12") (pintype "passive+no_connect"))
    )
    (net (code "302") (name "unconnected-(U007-~SHDNWARN-Pad11)") (class "Default")
      (node (ref "U007") (pin "11") (pinfunction "~SHDNWARN_11") (pintype "passive+no_connect"))
    )
  )
)
